# dcdcboard-v1.net
KiCad netlist of a schematic drawn in EAGLE
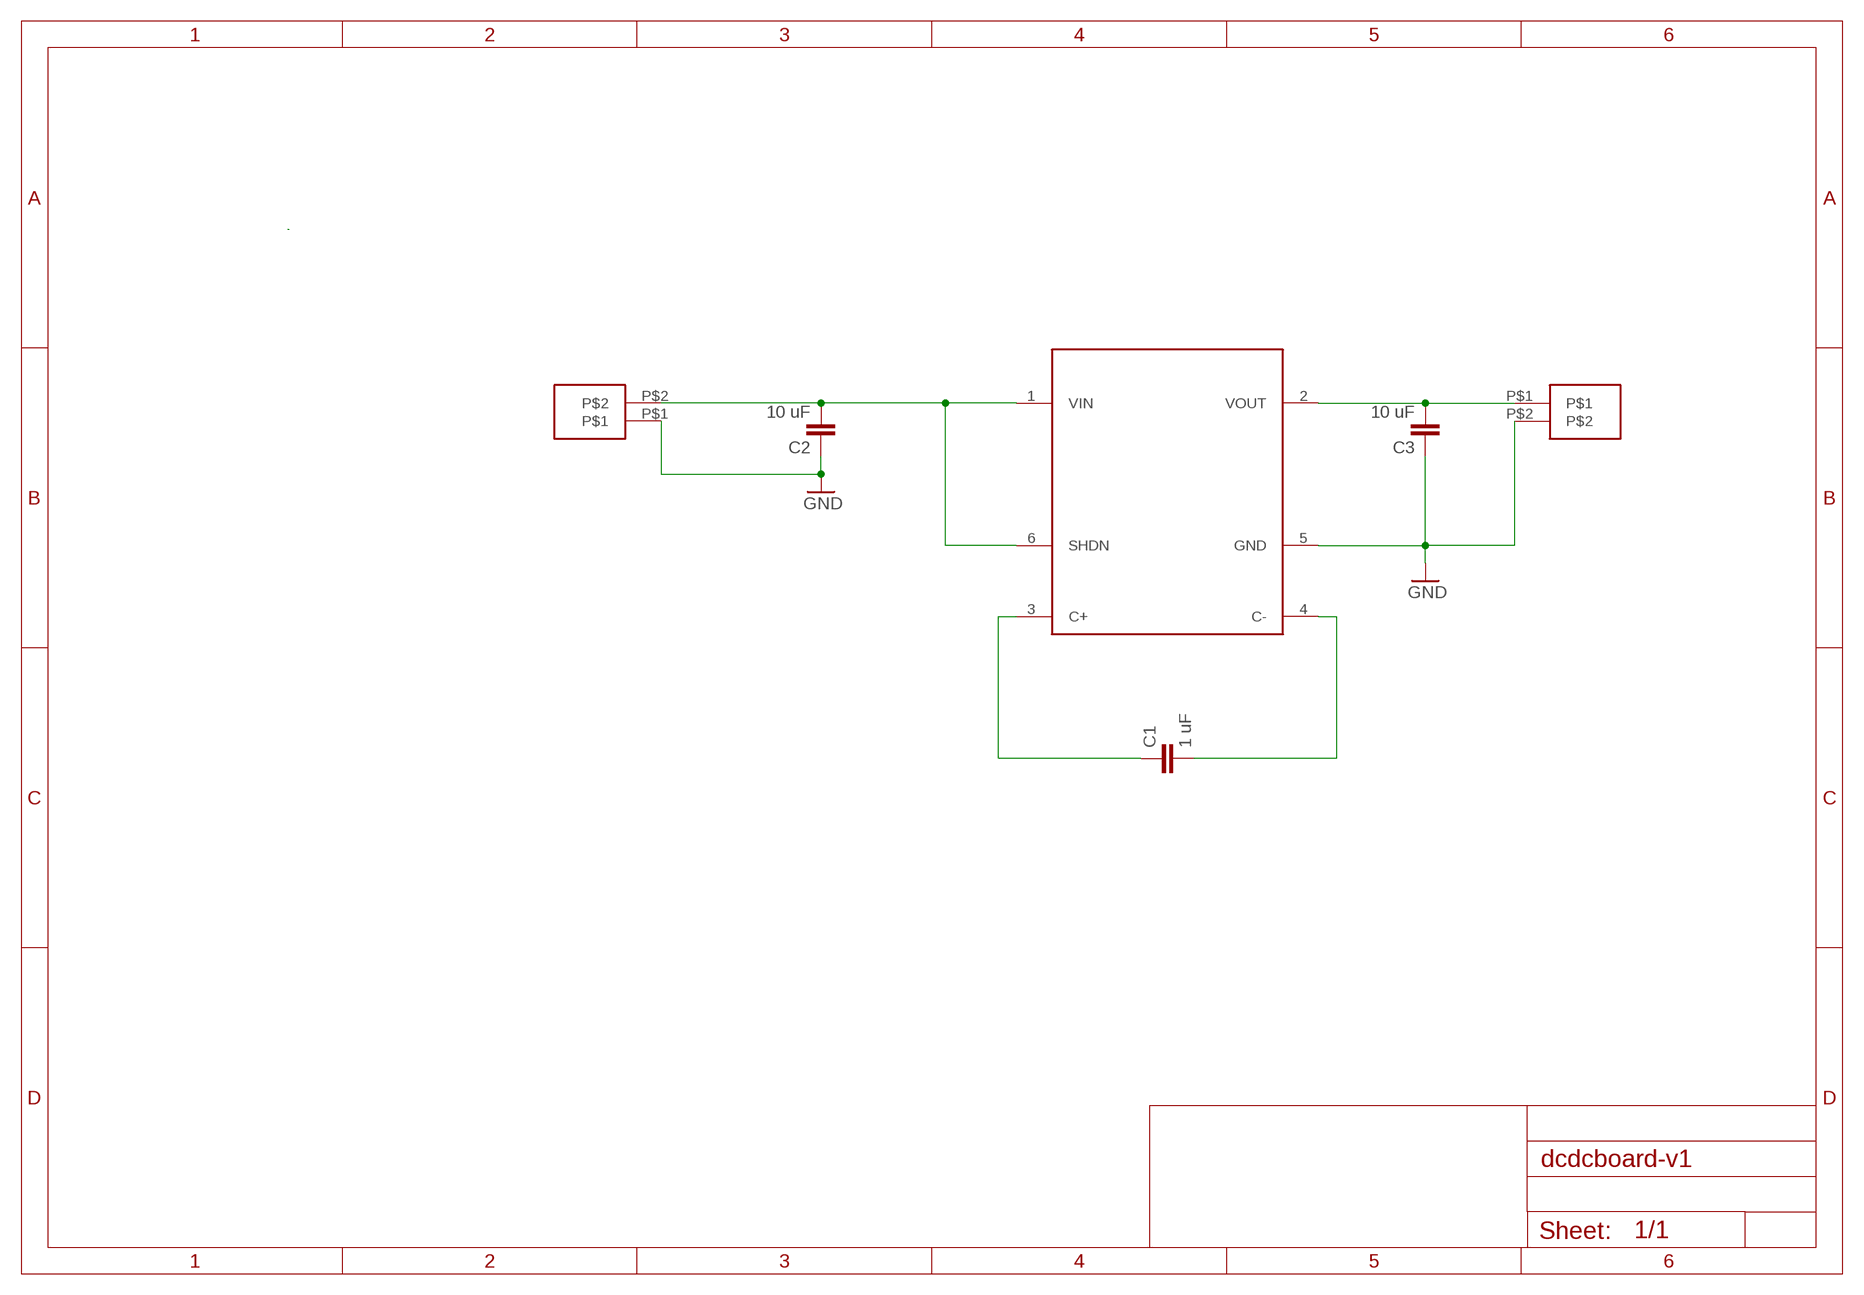
[diagram p0: schematic, sheet 1]

(export (version "E")
  (design (tool "Eeschema 10.0.6"))
  (components
    (comp (ref "C1")
      (value "1 uF")
      (footprint "eagle-import:0805")
      (libsource (lib "eagle-import") (part "CAP0805"))
    )
    (comp (ref "C2")
      (value "10 uF")
      (footprint "eagle-import:0805")
      (libsource (lib "eagle-import") (part "CAP0805"))
    )
    (comp (ref "C3")
      (value "10 uF")
      (footprint "eagle-import:0805")
      (libsource (lib "eagle-import") (part "CAP0805"))
    )
    (comp (ref "U$1")
      (value "LTC1983")
      (footprint "eagle-import:SSOT23-6")
      (libsource (lib "eagle-import") (part "LTC1983"))
    )
    (comp (ref "U$2")
      (value "SPRING-TERMINAL")
      (footprint "eagle-import:SPRING-TERMINAL")
      (libsource (lib "eagle-import") (part "SPRING-TERMINAL"))
    )
    (comp (ref "U$3")
      (value "SPRING-TERMINAL")
      (footprint "eagle-import:SPRING-TERMINAL")
      (libsource (lib "eagle-import") (part "SPRING-TERMINAL"))
    )
  )
  (nets
    (net (code "1") (name "GND") (class "Default")
      (node (ref "C2") (pin "1") (pinfunction "1_1") (pintype "passive"))
      (node (ref "C3") (pin "1") (pinfunction "1_1") (pintype "passive"))
      (node (ref "U$1") (pin "5") (pinfunction "GND_5") (pintype "bidirectional"))
      (node (ref "U$2") (pin "P$1") (pinfunction "P$1_P$1") (pintype "bidirectional"))
      (node (ref "U$3") (pin "P$2") (pinfunction "P$2_P$2") (pintype "bidirectional"))
    )
    (net (code "2") (name "Net-(U$1-C+)") (class "Default")
      (node (ref "C1") (pin "1") (pinfunction "1_1") (pintype "passive"))
      (node (ref "U$1") (pin "3") (pinfunction "C+_3") (pintype "bidirectional"))
    )
    (net (code "3") (name "Net-(U$1-C-)") (class "Default")
      (node (ref "C1") (pin "2") (pinfunction "2_2") (pintype "passive"))
      (node (ref "U$1") (pin "4") (pinfunction "C-_4") (pintype "bidirectional"))
    )
    (net (code "4") (name "Net-(U$1-SHDN)") (class "Default")
      (node (ref "C2") (pin "2") (pinfunction "2_2") (pintype "passive"))
      (node (ref "U$1") (pin "1") (pinfunction "VIN_1") (pintype "bidirectional"))
      (node (ref "U$1") (pin "6") (pinfunction "SHDN_6") (pintype "bidirectional"))
      (node (ref "U$2") (pin "P$2") (pinfunction "P$2_P$2") (pintype "bidirectional"))
    )
    (net (code "5") (name "Net-(U$1-VOUT)") (class "Default")
      (node (ref "C3") (pin "2") (pinfunction "2_2") (pintype "passive"))
      (node (ref "U$1") (pin "2") (pinfunction "VOUT_2") (pintype "bidirectional"))
      (node (ref "U$3") (pin "P$1") (pinfunction "P$1_P$1") (pintype "bidirectional"))
    )
  )
)
